# toslink_reciever.net
KiCad netlist of a schematic drawn in EAGLE
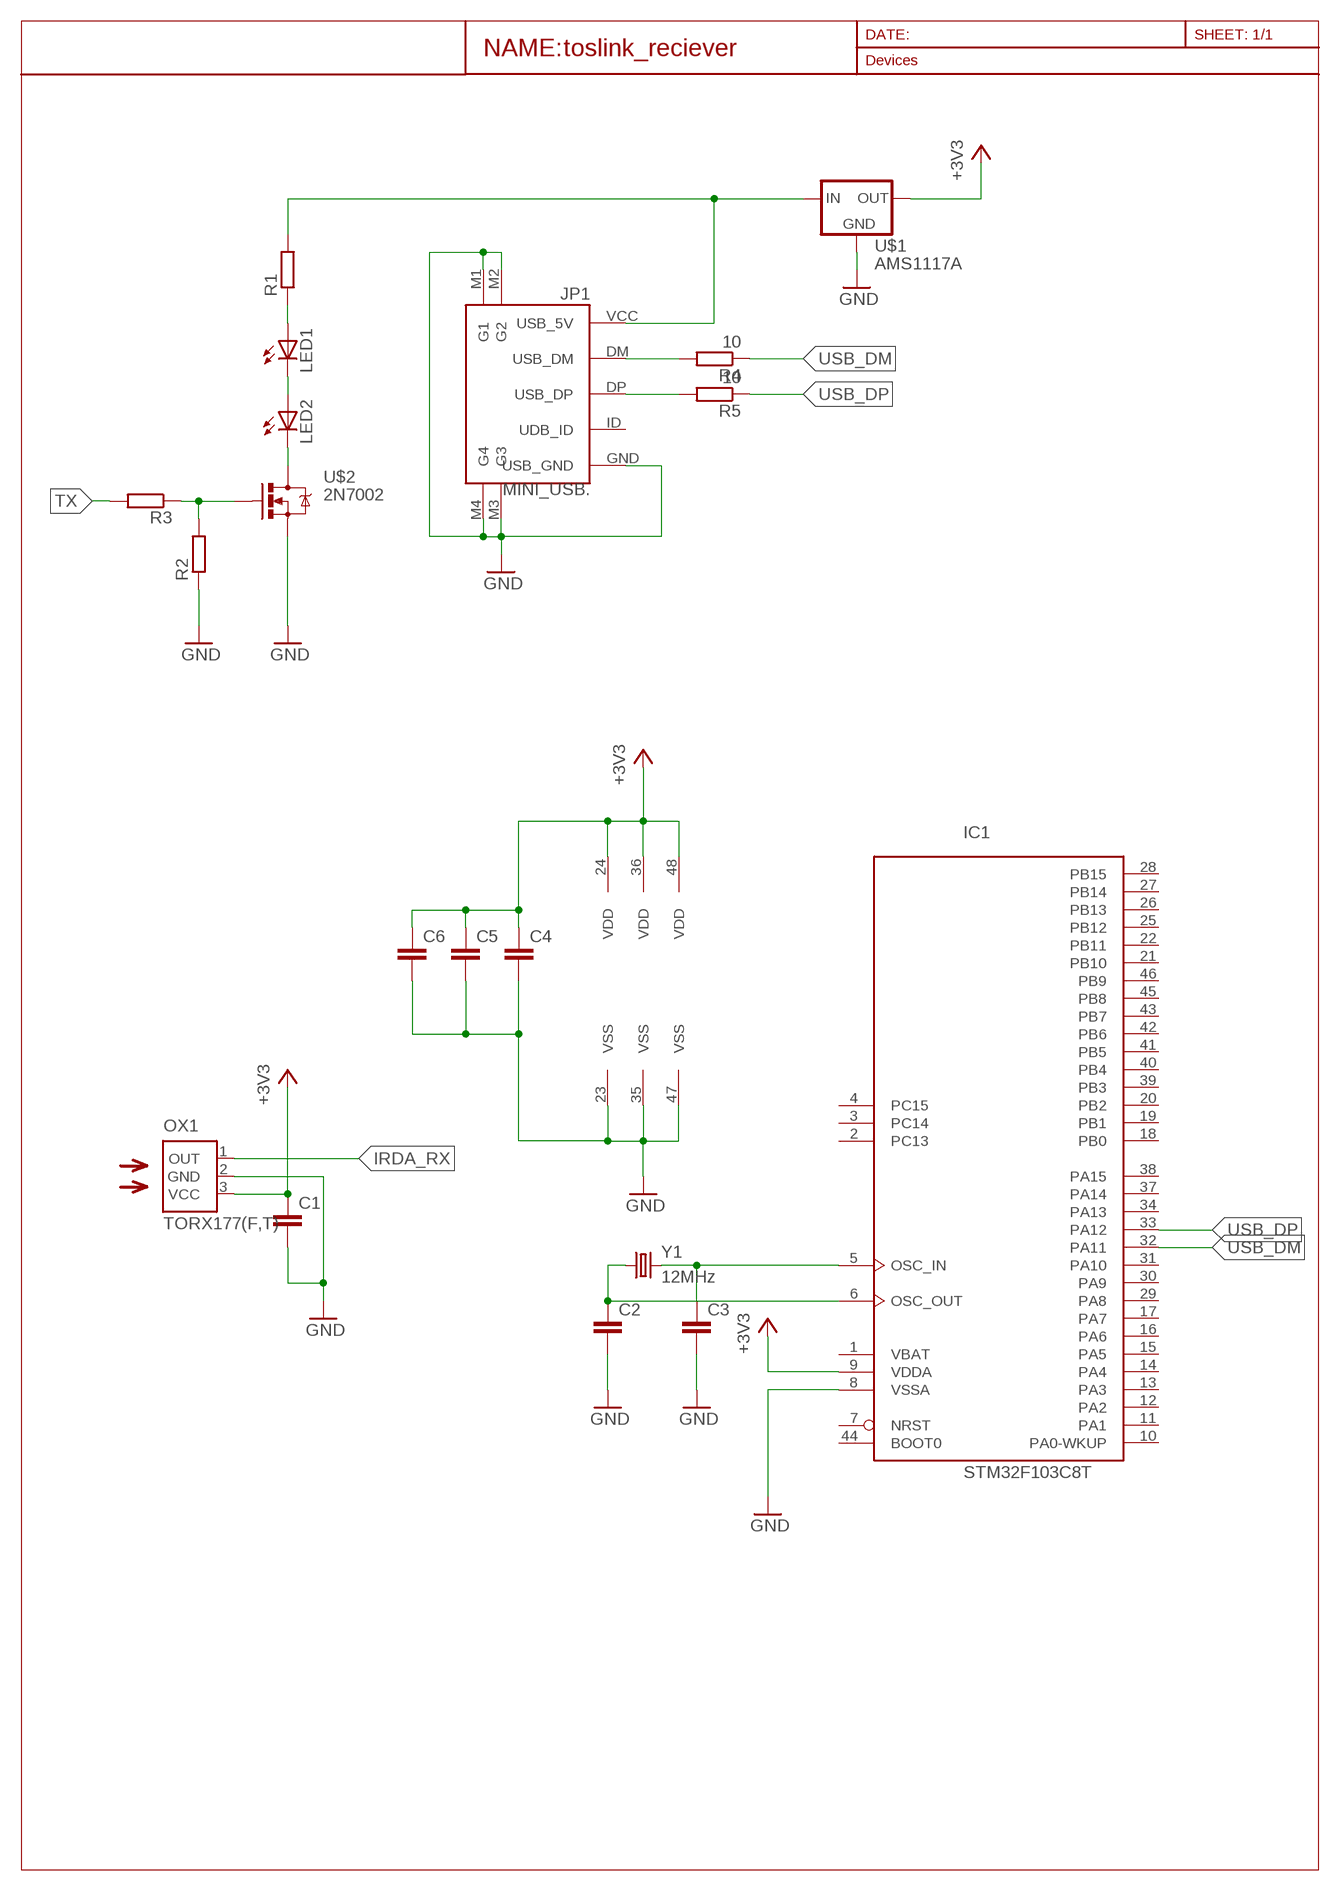
[diagram p0: schematic, sheet 1]

(export (version "E")
  (design (tool "Eeschema 10.0.6"))
  (components
    (comp (ref "C1")
      (value "CC0805")
      (footprint "eagle-import:C0805")
      (libsource (lib "eagle-import") (part "CC0805"))
    )
    (comp (ref "C2")
      (value "CC0603")
      (footprint "eagle-import:C0603")
      (libsource (lib "eagle-import") (part "CC0603"))
    )
    (comp (ref "C3")
      (value "CC0603")
      (footprint "eagle-import:C0603")
      (libsource (lib "eagle-import") (part "CC0603"))
    )
    (comp (ref "C4")
      (value "CC0805")
      (footprint "eagle-import:C0805")
      (libsource (lib "eagle-import") (part "CC0805"))
    )
    (comp (ref "C5")
      (value "CC0805")
      (footprint "eagle-import:C0805")
      (libsource (lib "eagle-import") (part "CC0805"))
    )
    (comp (ref "C6")
      (value "CC0805")
      (footprint "eagle-import:C0805")
      (libsource (lib "eagle-import") (part "CC0805"))
    )
    (comp (ref "IC1")
      (value "STM32F103C8T")
      (footprint "eagle-import:LQFP48")
      (libsource (lib "eagle-import") (part "STM32F103CT8"))
    )
    (comp (ref "JP1")
      (value "MINI_USB.")
      (footprint "eagle-import:32005-201")
      (libsource (lib "eagle-import") (part "MINI_USB."))
    )
    (comp (ref "LED1")
      (value "LED5MM")
      (footprint "eagle-import:LED5MM")
      (libsource (lib "eagle-import") (part "LED5MM"))
    )
    (comp (ref "LED2")
      (value "LED5MM")
      (footprint "eagle-import:LED5MM")
      (libsource (lib "eagle-import") (part "LED5MM"))
    )
    (comp (ref "OX1")
      (value "TORX177(F,T)")
      (footprint "eagle-import:TORX")
      (libsource (lib "eagle-import") (part "TORX177(F,T)"))
    )
    (comp (ref "R1")
      (value "R0603")
      (footprint "eagle-import:0603")
      (libsource (lib "eagle-import") (part "R0603"))
    )
    (comp (ref "R2")
      (value "R0603")
      (footprint "eagle-import:0603")
      (libsource (lib "eagle-import") (part "R0603"))
    )
    (comp (ref "R3")
      (value "R0603")
      (footprint "eagle-import:0603")
      (libsource (lib "eagle-import") (part "R0603"))
    )
    (comp (ref "R4")
      (value "10")
      (footprint "eagle-import:0603")
      (libsource (lib "eagle-import") (part "R0603"))
    )
    (comp (ref "R5")
      (value "10")
      (footprint "eagle-import:0603")
      (libsource (lib "eagle-import") (part "R0603"))
    )
    (comp (ref "U$1")
      (value "AMS1117A")
      (footprint "eagle-import:DPACK")
      (libsource (lib "eagle-import") (part "AMS1117A"))
    )
    (comp (ref "U$2")
      (value "2N7002")
      (footprint "eagle-import:SOT23")
      (libsource (lib "eagle-import") (part "2N7002"))
    )
    (comp (ref "Y1")
      (value "12MHz")
      (footprint "eagle-import:CRYSTAL-SMD-5X3")
      (libsource (lib "eagle-import") (part "CRYSTALCRYSTAL-SMD-5X3-12MHZ"))
    )
  )
  (nets
    (net (code "1") (name "+3V3") (class "Default")
      (node (ref "C1") (pin "1") (pinfunction "1_1") (pintype "passive"))
      (node (ref "C4") (pin "1") (pinfunction "1_1") (pintype "passive"))
      (node (ref "C5") (pin "1") (pinfunction "1_1") (pintype "passive"))
      (node (ref "C6") (pin "1") (pinfunction "1_1") (pintype "passive"))
      (node (ref "IC1") (pin "24") (pinfunction "VDD_24") (pintype "power_in"))
      (node (ref "IC1") (pin "36") (pinfunction "VDD_36") (pintype "power_in"))
      (node (ref "IC1") (pin "48") (pinfunction "VDD_48") (pintype "power_in"))
      (node (ref "IC1") (pin "9") (pinfunction "VDDA_9") (pintype "power_in"))
      (node (ref "OX1") (pin "3") (pinfunction "VCC_3") (pintype "power_in"))
      (node (ref "U$1") (pin "2") (pinfunction "OUT_2") (pintype "passive"))
    )
    (net (code "2") (name "/VBAT") (class "Default")
      (node (ref "IC1") (pin "1") (pinfunction "VBAT_1") (pintype "power_in"))
    )
    (net (code "3") (name "GND") (class "Default")
      (node (ref "C1") (pin "2") (pinfunction "2_2") (pintype "passive"))
      (node (ref "C2") (pin "2") (pinfunction "2_2") (pintype "passive"))
      (node (ref "C3") (pin "2") (pinfunction "2_2") (pintype "passive"))
      (node (ref "C4") (pin "2") (pinfunction "2_2") (pintype "passive"))
      (node (ref "C5") (pin "2") (pinfunction "2_2") (pintype "passive"))
      (node (ref "C6") (pin "2") (pinfunction "2_2") (pintype "passive"))
      (node (ref "IC1") (pin "23") (pinfunction "VSS_23") (pintype "power_in"))
      (node (ref "IC1") (pin "35") (pinfunction "VSS_35") (pintype "power_in"))
      (node (ref "IC1") (pin "47") (pinfunction "VSS_47") (pintype "power_in"))
      (node (ref "IC1") (pin "8") (pinfunction "VSSA_8") (pintype "power_in"))
      (node (ref "JP1") (pin "GND") (pinfunction "USB_GND_GND") (pintype "power_in"))
      (node (ref "JP1") (pin "M1") (pinfunction "G1_M1") (pintype "bidirectional"))
      (node (ref "JP1") (pin "M2") (pinfunction "G2_M2") (pintype "bidirectional"))
      (node (ref "JP1") (pin "M3") (pinfunction "G3_M3") (pintype "bidirectional"))
      (node (ref "JP1") (pin "M4") (pinfunction "G4_M4") (pintype "bidirectional"))
      (node (ref "OX1") (pin "2") (pinfunction "GND_2") (pintype "power_in"))
      (node (ref "R2") (pin "1") (pinfunction "1_1") (pintype "passive"))
      (node (ref "U$1") (pin "1") (pinfunction "GND_1") (pintype "input"))
      (node (ref "U$2") (pin "2") (pinfunction "S_2") (pintype "passive"))
    )
    (net (code "4") (name "IRDA_RX") (class "Default")
      (node (ref "OX1") (pin "1") (pinfunction "OUT_1") (pintype "output"))
    )
    (net (code "5") (name "Net-(IC1A-OSC_IN)") (class "Default")
      (node (ref "C3") (pin "1") (pinfunction "1_1") (pintype "passive"))
      (node (ref "IC1") (pin "5") (pinfunction "OSC_IN_5") (pintype "bidirectional"))
      (node (ref "Y1") (pin "3") (pinfunction "2_3") (pintype "passive"))
    )
    (net (code "6") (name "Net-(IC1A-OSC_OUT)") (class "Default")
      (node (ref "C2") (pin "1") (pinfunction "1_1") (pintype "passive"))
      (node (ref "IC1") (pin "6") (pinfunction "OSC_OUT_6") (pintype "bidirectional"))
      (node (ref "Y1") (pin "1") (pinfunction "1_1") (pintype "passive"))
    )
    (net (code "7") (name "Net-(JP1-USB_5V)") (class "Default")
      (node (ref "JP1") (pin "VCC") (pinfunction "USB_5V_VCC") (pintype "power_in"))
      (node (ref "R1") (pin "2") (pinfunction "2_2") (pintype "passive"))
      (node (ref "U$1") (pin "3") (pinfunction "IN_3") (pintype "input"))
    )
    (net (code "8") (name "Net-(JP1-USB_DM)") (class "Default")
      (node (ref "JP1") (pin "DM") (pinfunction "USB_DM_DM") (pintype "bidirectional"))
      (node (ref "R4") (pin "2") (pinfunction "2_2") (pintype "passive"))
    )
    (net (code "9") (name "Net-(JP1-USB_DP)") (class "Default")
      (node (ref "JP1") (pin "DP") (pinfunction "USB_DP_DP") (pintype "bidirectional"))
      (node (ref "R5") (pin "2") (pinfunction "2_2") (pintype "passive"))
    )
    (net (code "10") (name "Net-(LED1-C)") (class "Default")
      (node (ref "LED1") (pin "K") (pinfunction "C_K") (pintype "passive"))
      (node (ref "LED2") (pin "A") (pinfunction "A_A") (pintype "passive"))
    )
    (net (code "11") (name "Net-(LED1-PadA)") (class "Default")
      (node (ref "LED1") (pin "A") (pinfunction "A_A") (pintype "passive"))
      (node (ref "R1") (pin "1") (pinfunction "1_1") (pintype "passive"))
    )
    (net (code "12") (name "Net-(LED2-C)") (class "Default")
      (node (ref "LED2") (pin "K") (pinfunction "C_K") (pintype "passive"))
      (node (ref "U$2") (pin "3") (pinfunction "D_3") (pintype "passive"))
    )
    (net (code "13") (name "Net-(U$2-G)") (class "Default")
      (node (ref "R2") (pin "2") (pinfunction "2_2") (pintype "passive"))
      (node (ref "R3") (pin "1") (pinfunction "1_1") (pintype "passive"))
      (node (ref "U$2") (pin "1") (pinfunction "G_1") (pintype "passive"))
    )
    (net (code "14") (name "TX") (class "Default")
      (node (ref "R3") (pin "2") (pinfunction "2_2") (pintype "passive"))
    )
    (net (code "15") (name "USB_DM") (class "Default")
      (node (ref "IC1") (pin "32") (pinfunction "PA11_32") (pintype "bidirectional"))
      (node (ref "R4") (pin "1") (pinfunction "1_1") (pintype "passive"))
    )
    (net (code "16") (name "USB_DP") (class "Default")
      (node (ref "IC1") (pin "33") (pinfunction "PA12_33") (pintype "bidirectional"))
      (node (ref "R5") (pin "1") (pinfunction "1_1") (pintype "passive"))
    )
    (net (code "17") (name "unconnected-(IC1A-BOOT0-Pad44)") (class "Default")
      (node (ref "IC1") (pin "44") (pinfunction "BOOT0_44") (pintype "input"))
    )
    (net (code "18") (name "unconnected-(IC1A-NRST-Pad7)") (class "Default")
      (node (ref "IC1") (pin "7") (pinfunction "NRST_7") (pintype "bidirectional"))
    )
    (net (code "19") (name "unconnected-(IC1A-PA0-WKUP-Pad10)") (class "Default")
      (node (ref "IC1") (pin "10") (pinfunction "PA0-WKUP_10") (pintype "bidirectional"))
    )
    (net (code "20") (name "unconnected-(IC1A-PA1-Pad11)") (class "Default")
      (node (ref "IC1") (pin "11") (pinfunction "PA1_11") (pintype "bidirectional"))
    )
    (net (code "21") (name "unconnected-(IC1A-PA2-Pad12)") (class "Default")
      (node (ref "IC1") (pin "12") (pinfunction "PA2_12") (pintype "bidirectional"))
    )
    (net (code "22") (name "unconnected-(IC1A-PA3-Pad13)") (class "Default")
      (node (ref "IC1") (pin "13") (pinfunction "PA3_13") (pintype "bidirectional"))
    )
    (net (code "23") (name "unconnected-(IC1A-PA4-Pad14)") (class "Default")
      (node (ref "IC1") (pin "14") (pinfunction "PA4_14") (pintype "bidirectional"))
    )
    (net (code "24") (name "unconnected-(IC1A-PA5-Pad15)") (class "Default")
      (node (ref "IC1") (pin "15") (pinfunction "PA5_15") (pintype "bidirectional"))
    )
    (net (code "25") (name "unconnected-(IC1A-PA6-Pad16)") (class "Default")
      (node (ref "IC1") (pin "16") (pinfunction "PA6_16") (pintype "bidirectional"))
    )
    (net (code "26") (name "unconnected-(IC1A-PA7-Pad17)") (class "Default")
      (node (ref "IC1") (pin "17") (pinfunction "PA7_17") (pintype "bidirectional"))
    )
    (net (code "27") (name "unconnected-(IC1A-PA8-Pad29)") (class "Default")
      (node (ref "IC1") (pin "29") (pinfunction "PA8_29") (pintype "bidirectional"))
    )
    (net (code "28") (name "unconnected-(IC1A-PA9-Pad30)") (class "Default")
      (node (ref "IC1") (pin "30") (pinfunction "PA9_30") (pintype "bidirectional"))
    )
    (net (code "29") (name "unconnected-(IC1A-PA10-Pad31)") (class "Default")
      (node (ref "IC1") (pin "31") (pinfunction "PA10_31") (pintype "bidirectional"))
    )
    (net (code "30") (name "unconnected-(IC1A-PA13-Pad34)") (class "Default")
      (node (ref "IC1") (pin "34") (pinfunction "PA13_34") (pintype "bidirectional"))
    )
    (net (code "31") (name "unconnected-(IC1A-PA14-Pad37)") (class "Default")
      (node (ref "IC1") (pin "37") (pinfunction "PA14_37") (pintype "bidirectional"))
    )
    (net (code "32") (name "unconnected-(IC1A-PA15-Pad38)") (class "Default")
      (node (ref "IC1") (pin "38") (pinfunction "PA15_38") (pintype "bidirectional"))
    )
    (net (code "33") (name "unconnected-(IC1A-PB0-Pad18)") (class "Default")
      (node (ref "IC1") (pin "18") (pinfunction "PB0_18") (pintype "bidirectional"))
    )
    (net (code "34") (name "unconnected-(IC1A-PB1-Pad19)") (class "Default")
      (node (ref "IC1") (pin "19") (pinfunction "PB1_19") (pintype "bidirectional"))
    )
    (net (code "35") (name "unconnected-(IC1A-PB2-Pad20)") (class "Default")
      (node (ref "IC1") (pin "20") (pinfunction "PB2_20") (pintype "bidirectional"))
    )
    (net (code "36") (name "unconnected-(IC1A-PB3-Pad39)") (class "Default")
      (node (ref "IC1") (pin "39") (pinfunction "PB3_39") (pintype "bidirectional"))
    )
    (net (code "37") (name "unconnected-(IC1A-PB4-Pad40)") (class "Default")
      (node (ref "IC1") (pin "40") (pinfunction "PB4_40") (pintype "bidirectional"))
    )
    (net (code "38") (name "unconnected-(IC1A-PB5-Pad41)") (class "Default")
      (node (ref "IC1") (pin "41") (pinfunction "PB5_41") (pintype "bidirectional"))
    )
    (net (code "39") (name "unconnected-(IC1A-PB6-Pad42)") (class "Default")
      (node (ref "IC1") (pin "42") (pinfunction "PB6_42") (pintype "bidirectional"))
    )
    (net (code "40") (name "unconnected-(IC1A-PB7-Pad43)") (class "Default")
      (node (ref "IC1") (pin "43") (pinfunction "PB7_43") (pintype "bidirectional"))
    )
    (net (code "41") (name "unconnected-(IC1A-PB8-Pad45)") (class "Default")
      (node (ref "IC1") (pin "45") (pinfunction "PB8_45") (pintype "bidirectional"))
    )
    (net (code "42") (name "unconnected-(IC1A-PB9-Pad46)") (class "Default")
      (node (ref "IC1") (pin "46") (pinfunction "PB9_46") (pintype "bidirectional"))
    )
    (net (code "43") (name "unconnected-(IC1A-PB10-Pad21)") (class "Default")
      (node (ref "IC1") (pin "21") (pinfunction "PB10_21") (pintype "bidirectional"))
    )
    (net (code "44") (name "unconnected-(IC1A-PB11-Pad22)") (class "Default")
      (node (ref "IC1") (pin "22") (pinfunction "PB11_22") (pintype "bidirectional"))
    )
    (net (code "45") (name "unconnected-(IC1A-PB12-Pad25)") (class "Default")
      (node (ref "IC1") (pin "25") (pinfunction "PB12_25") (pintype "bidirectional"))
    )
    (net (code "46") (name "unconnected-(IC1A-PB13-Pad26)") (class "Default")
      (node (ref "IC1") (pin "26") (pinfunction "PB13_26") (pintype "bidirectional"))
    )
    (net (code "47") (name "unconnected-(IC1A-PB14-Pad27)") (class "Default")
      (node (ref "IC1") (pin "27") (pinfunction "PB14_27") (pintype "bidirectional"))
    )
    (net (code "48") (name "unconnected-(IC1A-PB15-Pad28)") (class "Default")
      (node (ref "IC1") (pin "28") (pinfunction "PB15_28") (pintype "bidirectional"))
    )
    (net (code "49") (name "unconnected-(IC1A-PC13-Pad2)") (class "Default")
      (node (ref "IC1") (pin "2") (pinfunction "PC13_2") (pintype "bidirectional"))
    )
    (net (code "50") (name "unconnected-(IC1A-PC14-Pad3)") (class "Default")
      (node (ref "IC1") (pin "3") (pinfunction "PC14_3") (pintype "bidirectional"))
    )
    (net (code "51") (name "unconnected-(IC1A-PC15-Pad4)") (class "Default")
      (node (ref "IC1") (pin "4") (pinfunction "PC15_4") (pintype "bidirectional"))
    )
    (net (code "52") (name "unconnected-(JP1-UDB_ID-PadID)") (class "Default")
      (node (ref "JP1") (pin "ID") (pinfunction "UDB_ID_ID") (pintype "bidirectional"))
    )
  )
)
